# boardV2.net
KiCad netlist of a schematic drawn in EAGLE
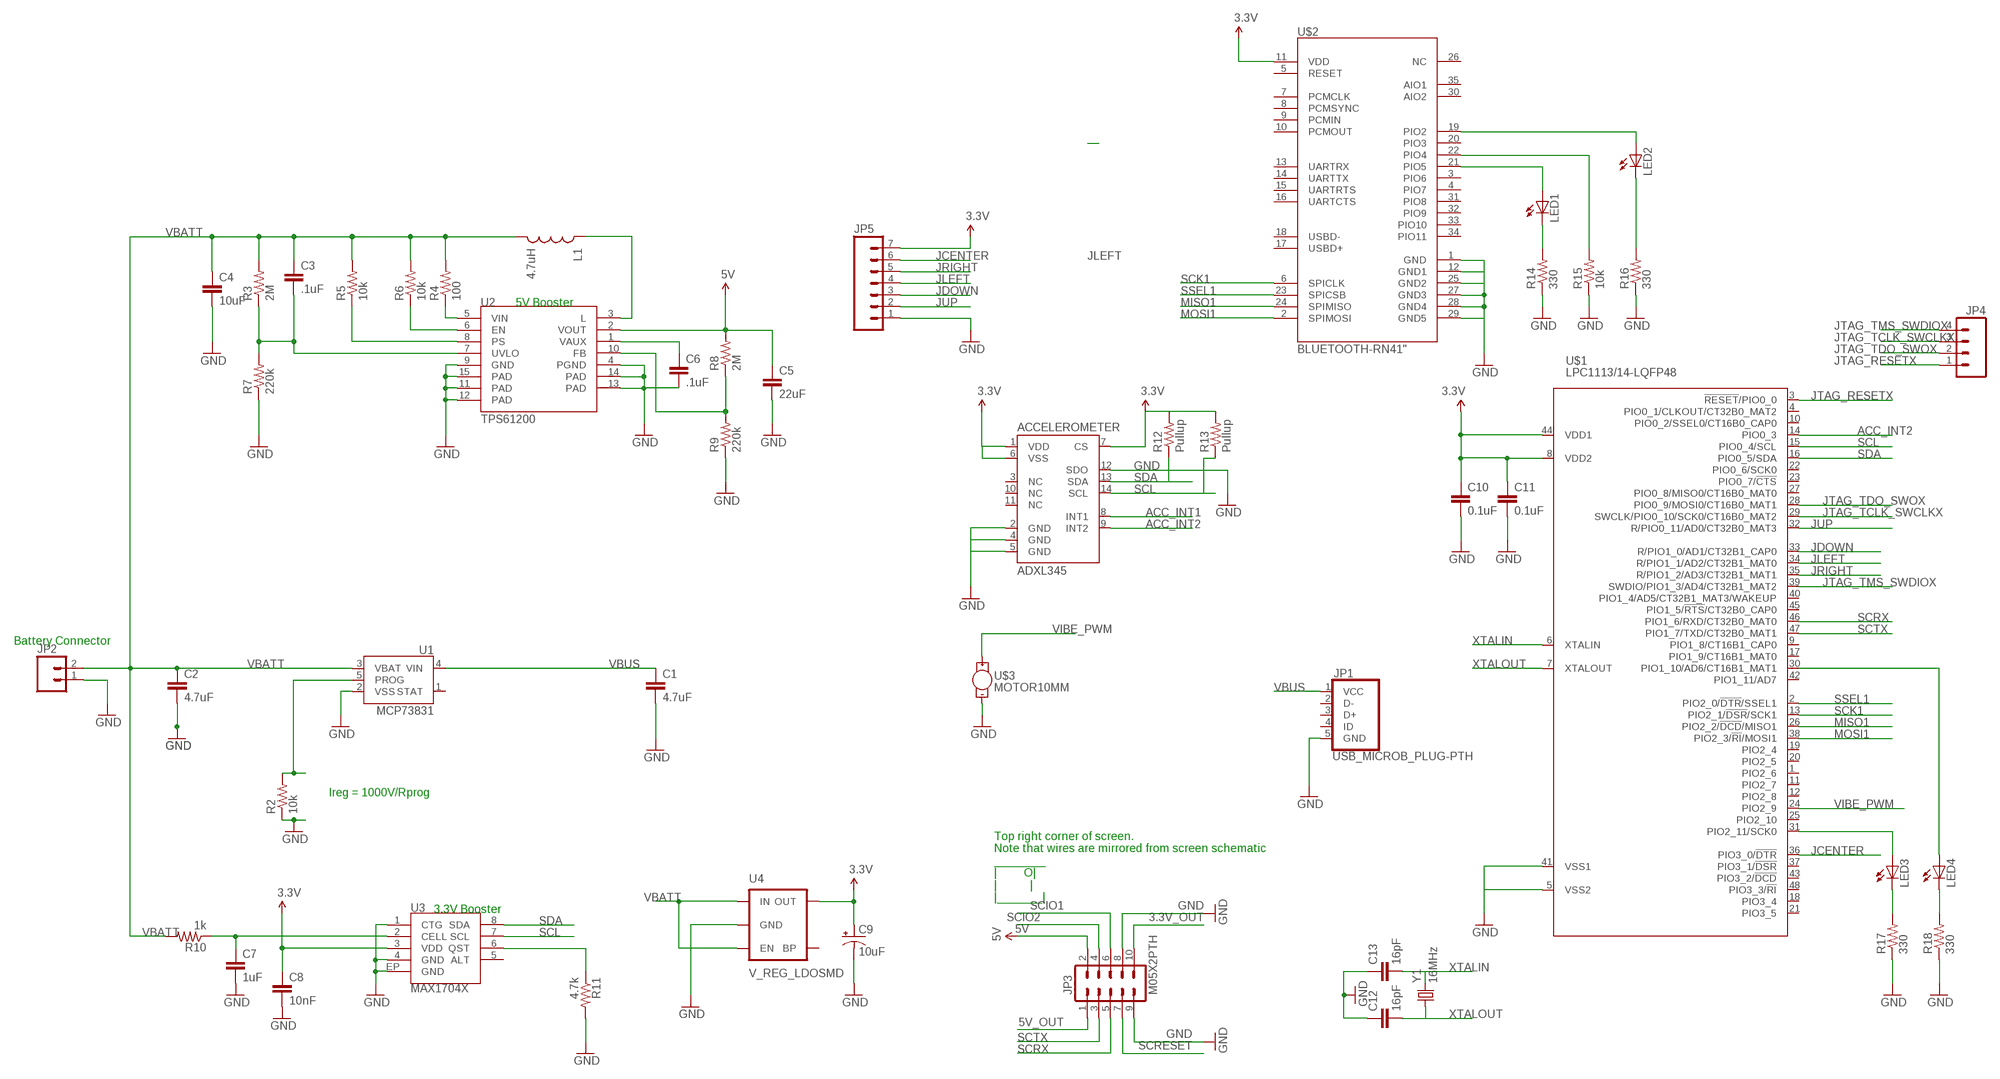
[diagram p0: schematic, sheet 1]

(export (version "E")
  (design (tool "Eeschema 10.0.6"))
  (components
    (comp (ref "ACCELEROMETER")
      (value "ADXL345")
      (footprint "eagle-import:LGA14")
      (libsource (lib "eagle-import") (part "ADXL345"))
    )
    (comp (ref "C1")
      (value "4.7uF")
      (footprint "eagle-import:0402-CAP")
      (libsource (lib "eagle-import") (part "CAP0402-CAP"))
    )
    (comp (ref "C2")
      (value "4.7uF")
      (footprint "eagle-import:0402-CAP")
      (libsource (lib "eagle-import") (part "CAP0402-CAP"))
    )
    (comp (ref "C3")
      (value ".1uF")
      (footprint "eagle-import:0402-CAP")
      (libsource (lib "eagle-import") (part "CAP0402-CAP"))
    )
    (comp (ref "C4")
      (value "10uF")
      (footprint "eagle-import:0402-CAP")
      (libsource (lib "eagle-import") (part "CAP0402-CAP"))
    )
    (comp (ref "C5")
      (value "22uF")
      (footprint "eagle-import:0402-CAP")
      (libsource (lib "eagle-import") (part "CAP0402-CAP"))
    )
    (comp (ref "C6")
      (value ".1uF")
      (footprint "eagle-import:0402-CAP")
      (libsource (lib "eagle-import") (part "CAP0402-CAP"))
    )
    (comp (ref "C7")
      (value "1uF")
      (footprint "eagle-import:0402-CAP")
      (libsource (lib "eagle-import") (part "CAP0402-CAP"))
    )
    (comp (ref "C8")
      (value "10nF")
      (footprint "eagle-import:0402-CAP")
      (libsource (lib "eagle-import") (part "CAP0402-CAP"))
    )
    (comp (ref "C9")
      (value "10uF")
      (footprint "eagle-import:EIA3216")
      (libsource (lib "eagle-import") (part "10UF-TANT"))
    )
    (comp (ref "C10")
      (value "0.1uF")
      (footprint "eagle-import:0402-CAP")
      (libsource (lib "eagle-import") (part ".1UF-CER"))
    )
    (comp (ref "C11")
      (value "0.1uF")
      (footprint "eagle-import:0402-CAP")
      (libsource (lib "eagle-import") (part ".1UF-CER"))
    )
    (comp (ref "C12")
      (value "16pF")
      (footprint "eagle-import:0402-CAP")
      (libsource (lib "eagle-import") (part "CAP0402-CAP"))
    )
    (comp (ref "C13")
      (value "16pF")
      (footprint "eagle-import:0402-CAP")
      (libsource (lib "eagle-import") (part "CAP0402-CAP"))
    )
    (comp (ref "JP1")
      (value "USB_MICROB_PLUG-PTH")
      (footprint "eagle-import:MICRO-B-RA-TH")
      (libsource (lib "eagle-import") (part "USB_MICROB_PLUG-PTH"))
    )
    (comp (ref "JP2")
      (value "M02-JST-2-PTH-NO_SILK")
      (footprint "eagle-import:JST-2-PTH-NS")
      (libsource (lib "eagle-import") (part "M02-JST-2-PTH-NO_SILK"))
    )
    (comp (ref "JP3")
      (value "M05X2PTH")
      (footprint "eagle-import:AVR_ICSP")
      (libsource (lib "eagle-import") (part "M05X2PTH"))
    )
    (comp (ref "JP4")
      (value "M04POLAR")
      (footprint "eagle-import:MOLEX-1X4")
      (libsource (lib "eagle-import") (part "M04POLAR"))
    )
    (comp (ref "JP5")
      (value "M07")
      (footprint "eagle-import:1X07")
      (libsource (lib "eagle-import") (part "M07"))
    )
    (comp (ref "L1")
      (value "4.7uH")
      (footprint "eagle-import:C0402")
      (libsource (lib "eagle-import") (part "INDUCTOR0402"))
    )
    (comp (ref "LED1")
      (value "LED0603")
      (footprint "eagle-import:LED-0603")
      (libsource (lib "eagle-import") (part "LED0603"))
    )
    (comp (ref "LED2")
      (value "LED0603")
      (footprint "eagle-import:LED-0603")
      (libsource (lib "eagle-import") (part "LED0603"))
    )
    (comp (ref "LED3")
      (value "LED0603")
      (footprint "eagle-import:LED-0603")
      (libsource (lib "eagle-import") (part "LED0603"))
    )
    (comp (ref "LED4")
      (value "LED0603")
      (footprint "eagle-import:LED-0603")
      (libsource (lib "eagle-import") (part "LED0603"))
    )
    (comp (ref "R2")
      (value "10k")
      (footprint "eagle-import:0402-RES")
      (libsource (lib "eagle-import") (part "RESISTOR0402-RES"))
    )
    (comp (ref "R3")
      (value "2M")
      (footprint "eagle-import:0402-RES")
      (libsource (lib "eagle-import") (part "RESISTOR0402-RES"))
    )
    (comp (ref "R4")
      (value "100")
      (footprint "eagle-import:0402-RES")
      (libsource (lib "eagle-import") (part "RESISTOR0402-RES"))
    )
    (comp (ref "R5")
      (value "10k")
      (footprint "eagle-import:0402-RES")
      (libsource (lib "eagle-import") (part "RESISTOR0402-RES"))
    )
    (comp (ref "R6")
      (value "10k")
      (footprint "eagle-import:0402-RES")
      (libsource (lib "eagle-import") (part "RESISTOR0402-RES"))
    )
    (comp (ref "R7")
      (value "220k")
      (footprint "eagle-import:0402-RES")
      (libsource (lib "eagle-import") (part "RESISTOR0402-RES"))
    )
    (comp (ref "R8")
      (value "2M")
      (footprint "eagle-import:0402-RES")
      (libsource (lib "eagle-import") (part "RESISTOR0402-RES"))
    )
    (comp (ref "R9")
      (value "220k")
      (footprint "eagle-import:0402-RES")
      (libsource (lib "eagle-import") (part "RESISTOR0402-RES"))
    )
    (comp (ref "R10")
      (value "1k")
      (footprint "eagle-import:0402-RES")
      (libsource (lib "eagle-import") (part "RESISTOR0402-RES"))
    )
    (comp (ref "R11")
      (value "4.7k")
      (footprint "eagle-import:0402-RES")
      (libsource (lib "eagle-import") (part "RESISTOR0402-RES"))
    )
    (comp (ref "R12")
      (value "Pullup")
      (footprint "eagle-import:0402-RES")
      (libsource (lib "eagle-import") (part "RESISTOR0402-RES"))
    )
    (comp (ref "R13")
      (value "Pullup")
      (footprint "eagle-import:0402-RES")
      (libsource (lib "eagle-import") (part "RESISTOR0402-RES"))
    )
    (comp (ref "R14")
      (value "330")
      (footprint "eagle-import:0402-RES")
      (libsource (lib "eagle-import") (part "RESISTOR0402-RES"))
    )
    (comp (ref "R15")
      (value "10k")
      (footprint "eagle-import:0402-RES")
      (libsource (lib "eagle-import") (part "RESISTOR0402-RES"))
    )
    (comp (ref "R16")
      (value "330")
      (footprint "eagle-import:0402-RES")
      (libsource (lib "eagle-import") (part "RESISTOR0402-RES"))
    )
    (comp (ref "R17")
      (value "330")
      (footprint "eagle-import:0402-RES")
      (libsource (lib "eagle-import") (part "RESISTOR0402-RES"))
    )
    (comp (ref "R18")
      (value "330")
      (footprint "eagle-import:0402-RES")
      (libsource (lib "eagle-import") (part "RESISTOR0402-RES"))
    )
    (comp (ref "U$1")
      (value "LPC1113/14-LQFP48")
      (footprint "eagle-import:LQFP48")
      (libsource (lib "eagle-import") (part "LPC1113/14-LQFP48"))
    )
    (comp (ref "U$2")
      (value "BLUETOOTH-RN41\"")
      (footprint "eagle-import:RN41")
      (libsource (lib "eagle-import") (part "BLUETOOTH-RN41{dblquote}"))
    )
    (comp (ref "U$3")
      (value "MOTOR10MM")
      (footprint "eagle-import:VIBE-MOTOR-10MM")
      (libsource (lib "eagle-import") (part "MOTOR10MM"))
    )
    (comp (ref "U1")
      (value "MCP73831")
      (footprint "eagle-import:SOT23-5")
      (libsource (lib "eagle-import") (part "MCP73831"))
    )
    (comp (ref "U2")
      (value "TPS61200")
      (footprint "eagle-import:QFN-10_PAD")
      (libsource (lib "eagle-import") (part "TPS61200"))
    )
    (comp (ref "U3")
      (value "MAX1704X")
      (footprint "eagle-import:TDFN-8")
      (libsource (lib "eagle-import") (part "MAX1704X"))
    )
    (comp (ref "U4")
      (value "V_REG_LDOSMD")
      (footprint "eagle-import:SOT23-5")
      (libsource (lib "eagle-import") (part "V_REG_LDOSMD"))
    )
    (comp (ref "Y1")
      (value "16MHz")
      (footprint "eagle-import:CRYSTAL-SMD-5X3")
      (libsource (lib "eagle-import") (part "CRYSTAL5X3"))
    )
  )
  (nets
    (net (code "1") (name "/3.3V_OUT") (class "Default")
      (node (ref "JP3") (pin "10") (pinfunction "10_10") (pintype "passive"))
    )
    (net (code "2") (name "/5V_OUT") (class "Default")
      (node (ref "JP3") (pin "1") (pinfunction "1_1") (pintype "passive"))
    )
    (net (code "3") (name "/ACC_INT1") (class "Default")
      (node (ref "ACCELEROMETER") (pin "8") (pinfunction "INT1_8") (pintype "bidirectional"))
    )
    (net (code "4") (name "/ACC_INT2") (class "Default")
      (node (ref "ACCELEROMETER") (pin "9") (pinfunction "INT2_9") (pintype "bidirectional"))
      (node (ref "U$1") (pin "14") (pinfunction "PIO0_3_14") (pintype "bidirectional"))
    )
    (net (code "5") (name "/JCENTER") (class "Default")
      (node (ref "JP5") (pin "6") (pinfunction "6_6") (pintype "passive"))
      (node (ref "U$1") (pin "36") (pinfunction "PIO3_0/~{DTR}_36") (pintype "bidirectional"))
    )
    (net (code "6") (name "/JDOWN") (class "Default")
      (node (ref "JP5") (pin "3") (pinfunction "3_3") (pintype "passive"))
      (node (ref "U$1") (pin "33") (pinfunction "R/PIO1_0/AD1/CT32B1_CAP0_33") (pintype "bidirectional"))
    )
    (net (code "7") (name "/JLEFT") (class "Default")
      (node (ref "JP5") (pin "4") (pinfunction "4_4") (pintype "passive"))
      (node (ref "U$1") (pin "34") (pinfunction "R/PIO1_1/AD2/CT32B1_MAT0_34") (pintype "bidirectional"))
    )
    (net (code "8") (name "/JRIGHT") (class "Default")
      (node (ref "JP5") (pin "5") (pinfunction "5_5") (pintype "passive"))
      (node (ref "U$1") (pin "35") (pinfunction "R/PIO1_2/AD3/CT32B1_MAT1_35") (pintype "bidirectional"))
    )
    (net (code "9") (name "/JTAG_RESETX") (class "Default")
      (node (ref "JP4") (pin "1") (pinfunction "1_1") (pintype "passive"))
      (node (ref "U$1") (pin "3") (pinfunction "~{RESET}/PIO0_0_3") (pintype "bidirectional"))
    )
    (net (code "10") (name "/JTAG_TCLK_SWCLKX") (class "Default")
      (node (ref "JP4") (pin "3") (pinfunction "3_3") (pintype "passive"))
      (node (ref "U$1") (pin "29") (pinfunction "SWCLK/PIO0_10/SCK0/CT16B0_MAT2_29") (pintype "bidirectional"))
    )
    (net (code "11") (name "/JTAG_TDO_SWOX") (class "Default")
      (node (ref "JP4") (pin "2") (pinfunction "2_2") (pintype "passive"))
      (node (ref "U$1") (pin "28") (pinfunction "PIO0_9/MOSI0/CT16B0_MAT1_28") (pintype "bidirectional"))
    )
    (net (code "12") (name "/JTAG_TMS_SWDIOX") (class "Default")
      (node (ref "JP4") (pin "4") (pinfunction "4_4") (pintype "passive"))
      (node (ref "U$1") (pin "39") (pinfunction "SWDIO/PIO1_3/AD4/CT32B1_MAT2_39") (pintype "bidirectional"))
    )
    (net (code "13") (name "/JUP") (class "Default")
      (node (ref "JP5") (pin "2") (pinfunction "2_2") (pintype "passive"))
      (node (ref "U$1") (pin "32") (pinfunction "R/PIO0_11/AD0/CT32B0_MAT3_32") (pintype "bidirectional"))
    )
    (net (code "14") (name "/MISO1") (class "Default")
      (node (ref "U$1") (pin "26") (pinfunction "PIO2_2/~{DCD}/MISO1_26") (pintype "bidirectional"))
      (node (ref "U$2") (pin "24") (pinfunction "SPIMISO_24") (pintype "bidirectional"))
    )
    (net (code "15") (name "/MOSI1") (class "Default")
      (node (ref "U$1") (pin "38") (pinfunction "PIO2_3/~{RI}/MOSI1_38") (pintype "bidirectional"))
      (node (ref "U$2") (pin "2") (pinfunction "SPIMOSI_2") (pintype "bidirectional"))
    )
    (net (code "16") (name "/SCIO1") (class "Default")
      (node (ref "JP3") (pin "6") (pinfunction "6_6") (pintype "passive"))
    )
    (net (code "17") (name "/SCIO2") (class "Default")
      (node (ref "JP3") (pin "4") (pinfunction "4_4") (pintype "passive"))
    )
    (net (code "18") (name "/SCK1") (class "Default")
      (node (ref "U$1") (pin "13") (pinfunction "PIO2_1/~{DSR}/SCK1_13") (pintype "bidirectional"))
      (node (ref "U$2") (pin "6") (pinfunction "SPICLK_6") (pintype "bidirectional"))
    )
    (net (code "19") (name "/SCL") (class "Default")
      (node (ref "ACCELEROMETER") (pin "14") (pinfunction "SCL_14") (pintype "bidirectional"))
      (node (ref "R13") (pin "1") (pinfunction "1_1") (pintype "passive"))
      (node (ref "U$1") (pin "15") (pinfunction "PIO0_4/SCL_15") (pintype "bidirectional"))
      (node (ref "U3") (pin "7") (pinfunction "SCL_7") (pintype "bidirectional"))
    )
    (net (code "20") (name "/SCRESET") (class "Default")
      (node (ref "JP3") (pin "7") (pinfunction "7_7") (pintype "passive"))
    )
    (net (code "21") (name "/SCRX") (class "Default")
      (node (ref "JP3") (pin "5") (pinfunction "5_5") (pintype "passive"))
      (node (ref "U$1") (pin "46") (pinfunction "PIO1_6/RXD/CT32B0_MAT0_46") (pintype "bidirectional"))
    )
    (net (code "22") (name "/SCTX") (class "Default")
      (node (ref "JP3") (pin "3") (pinfunction "3_3") (pintype "passive"))
      (node (ref "U$1") (pin "47") (pinfunction "PIO1_7/TXD/CT32B0_MAT1_47") (pintype "bidirectional"))
    )
    (net (code "23") (name "/SDA") (class "Default")
      (node (ref "ACCELEROMETER") (pin "13") (pinfunction "SDA_13") (pintype "bidirectional"))
      (node (ref "R12") (pin "1") (pinfunction "1_1") (pintype "passive"))
      (node (ref "U$1") (pin "16") (pinfunction "PIO0_5/SDA_16") (pintype "bidirectional"))
      (node (ref "U3") (pin "8") (pinfunction "SDA_8") (pintype "bidirectional"))
    )
    (net (code "24") (name "/SSEL1") (class "Default")
      (node (ref "U$1") (pin "2") (pinfunction "PIO2_0/~{DTR}/SSEL1_2") (pintype "bidirectional"))
      (node (ref "U$2") (pin "23") (pinfunction "SPICSB_23") (pintype "bidirectional"))
    )
    (net (code "25") (name "/VBATT") (class "Default")
      (node (ref "C2") (pin "1") (pinfunction "1_1") (pintype "passive"))
      (node (ref "C3") (pin "1") (pinfunction "1_1") (pintype "passive"))
      (node (ref "C4") (pin "1") (pinfunction "1_1") (pintype "passive"))
      (node (ref "JP2") (pin "2") (pinfunction "2_2") (pintype "passive"))
      (node (ref "L1") (pin "2") (pinfunction "2_2") (pintype "passive"))
      (node (ref "R10") (pin "2") (pinfunction "2_2") (pintype "passive"))
      (node (ref "R3") (pin "2") (pinfunction "2_2") (pintype "passive"))
      (node (ref "R4") (pin "2") (pinfunction "2_2") (pintype "passive"))
      (node (ref "R5") (pin "2") (pinfunction "2_2") (pintype "passive"))
      (node (ref "R6") (pin "2") (pinfunction "2_2") (pintype "passive"))
      (node (ref "U1") (pin "3") (pinfunction "VBAT_3") (pintype "power_in"))
      (node (ref "U4") (pin "1") (pinfunction "IN_1") (pintype "input"))
      (node (ref "U4") (pin "3") (pinfunction "EN_3") (pintype "input"))
    )
    (net (code "26") (name "/VBUS") (class "Default")
      (node (ref "C1") (pin "1") (pinfunction "1_1") (pintype "passive"))
      (node (ref "JP1") (pin "1") (pinfunction "VCC_1") (pintype "bidirectional"))
      (node (ref "U1") (pin "4") (pinfunction "VIN_4") (pintype "power_in"))
    )
    (net (code "27") (name "/VIBE_PWM") (class "Default")
      (node (ref "U$1") (pin "24") (pinfunction "PIO2_9_24") (pintype "bidirectional"))
      (node (ref "U$3") (pin "+") (pinfunction "+_+") (pintype "bidirectional"))
    )
    (net (code "28") (name "/XTALIN") (class "Default")
      (node (ref "C13") (pin "2") (pinfunction "2_2") (pintype "passive"))
      (node (ref "U$1") (pin "6") (pinfunction "XTALIN_6") (pintype "passive"))
      (node (ref "Y1") (pin "3") (pinfunction "2_3") (pintype "passive"))
    )
    (net (code "29") (name "/XTALOUT") (class "Default")
      (node (ref "C12") (pin "2") (pinfunction "2_2") (pintype "passive"))
      (node (ref "U$1") (pin "7") (pinfunction "XTALOUT_7") (pintype "passive"))
      (node (ref "Y1") (pin "1") (pinfunction "1_1") (pintype "passive"))
    )
    (net (code "30") (name "3.3V") (class "Default")
      (node (ref "ACCELEROMETER") (pin "1") (pinfunction "VDD_1") (pintype "bidirectional"))
      (node (ref "ACCELEROMETER") (pin "6") (pinfunction "VSS_6") (pintype "bidirectional"))
      (node (ref "ACCELEROMETER") (pin "7") (pinfunction "CS_7") (pintype "bidirectional"))
      (node (ref "C10") (pin "1") (pinfunction "1_1") (pintype "passive"))
      (node (ref "C11") (pin "1") (pinfunction "1_1") (pintype "passive"))
      (node (ref "C8") (pin "1") (pinfunction "1_1") (pintype "passive"))
      (node (ref "C9") (pin "A") (pinfunction "+_A") (pintype "passive"))
      (node (ref "JP5") (pin "7") (pinfunction "7_7") (pintype "passive"))
      (node (ref "R12") (pin "2") (pinfunction "2_2") (pintype "passive"))
      (node (ref "R13") (pin "2") (pinfunction "2_2") (pintype "passive"))
      (node (ref "U$1") (pin "44") (pinfunction "VDD1_44") (pintype "power_in"))
      (node (ref "U$1") (pin "8") (pinfunction "VDD2_8") (pintype "power_in"))
      (node (ref "U$2") (pin "11") (pinfunction "VDD_11") (pintype "bidirectional"))
      (node (ref "U3") (pin "3") (pinfunction "VDD_3") (pintype "bidirectional"))
      (node (ref "U4") (pin "5") (pinfunction "OUT_5") (pintype "passive"))
    )
    (net (code "31") (name "5V") (class "Default")
      (node (ref "C5") (pin "1") (pinfunction "1_1") (pintype "passive"))
      (node (ref "JP3") (pin "2") (pinfunction "2_2") (pintype "passive"))
      (node (ref "R8") (pin "2") (pinfunction "2_2") (pintype "passive"))
      (node (ref "U2") (pin "2") (pinfunction "VOUT_2") (pintype "passive"))
    )
    (net (code "32") (name "GND") (class "Default")
      (node (ref "ACCELEROMETER") (pin "12") (pinfunction "SDO_12") (pintype "bidirectional"))
      (node (ref "ACCELEROMETER") (pin "2") (pinfunction "GND_2") (pintype "bidirectional"))
      (node (ref "ACCELEROMETER") (pin "4") (pinfunction "GND_4") (pintype "bidirectional"))
      (node (ref "ACCELEROMETER") (pin "5") (pinfunction "GND_5") (pintype "bidirectional"))
      (node (ref "C1") (pin "2") (pinfunction "2_2") (pintype "passive"))
      (node (ref "C10") (pin "2") (pinfunction "2_2") (pintype "passive"))
      (node (ref "C11") (pin "2") (pinfunction "2_2") (pintype "passive"))
      (node (ref "C12") (pin "1") (pinfunction "1_1") (pintype "passive"))
      (node (ref "C13") (pin "1") (pinfunction "1_1") (pintype "passive"))
      (node (ref "C2") (pin "2") (pinfunction "2_2") (pintype "passive"))
      (node (ref "C4") (pin "2") (pinfunction "2_2") (pintype "passive"))
      (node (ref "C5") (pin "2") (pinfunction "2_2") (pintype "passive"))
      (node (ref "C6") (pin "2") (pinfunction "2_2") (pintype "passive"))
      (node (ref "C7") (pin "2") (pinfunction "2_2") (pintype "passive"))
      (node (ref "C8") (pin "2") (pinfunction "2_2") (pintype "passive"))
      (node (ref "C9") (pin "C") (pinfunction "-_C") (pintype "passive"))
      (node (ref "JP1") (pin "5") (pinfunction "GND_5") (pintype "bidirectional"))
      (node (ref "JP2") (pin "1") (pinfunction "1_1") (pintype "passive"))
      (node (ref "JP3") (pin "8") (pinfunction "8_8") (pintype "passive"))
      (node (ref "JP3") (pin "9") (pinfunction "9_9") (pintype "passive"))
      (node (ref "JP5") (pin "1") (pinfunction "1_1") (pintype "passive"))
      (node (ref "R11") (pin "2") (pinfunction "2_2") (pintype "passive"))
      (node (ref "R14") (pin "1") (pinfunction "1_1") (pintype "passive"))
      (node (ref "R15") (pin "1") (pinfunction "1_1") (pintype "passive"))
      (node (ref "R16") (pin "1") (pinfunction "1_1") (pintype "passive"))
      (node (ref "R17") (pin "1") (pinfunction "1_1") (pintype "passive"))
      (node (ref "R18") (pin "1") (pinfunction "1_1") (pintype "passive"))
      (node (ref "R2") (pin "1") (pinfunction "1_1") (pintype "passive"))
      (node (ref "R7") (pin "1") (pinfunction "1_1") (pintype "passive"))
      (node (ref "R9") (pin "1") (pinfunction "1_1") (pintype "passive"))
      (node (ref "U$1") (pin "41") (pinfunction "VSS1_41") (pintype "power_in"))
      (node (ref "U$1") (pin "5") (pinfunction "VSS2_5") (pintype "power_in"))
      (node (ref "U$2") (pin "1") (pinfunction "GND_1") (pintype "bidirectional"))
      (node (ref "U$2") (pin "12") (pinfunction "GND1_12") (pintype "bidirectional"))
      (node (ref "U$2") (pin "25") (pinfunction "GND2_25") (pintype "bidirectional"))
      (node (ref "U$2") (pin "27") (pinfunction "GND3_27") (pintype "bidirectional"))
      (node (ref "U$2") (pin "28") (pinfunction "GND4_28") (pintype "bidirectional"))
      (node (ref "U$2") (pin "29") (pinfunction "GND5_29") (pintype "bidirectional"))
      (node (ref "U$3") (pin "-") (pinfunction "-_-") (pintype "bidirectional"))
      (node (ref "U1") (pin "2") (pinfunction "VSS_2") (pintype "power_in"))
      (node (ref "U2") (pin "11") (pinfunction "PAD_11") (pintype "power_in"))
      (node (ref "U2") (pin "12") (pinfunction "PAD_12") (pintype "power_in"))
      (node (ref "U2") (pin "13") (pinfunction "PAD_13") (pintype "power_in"))
      (node (ref "U2") (pin "14") (pinfunction "PAD_14") (pintype "power_in"))
      (node (ref "U2") (pin "15") (pinfunction "PAD_15") (pintype "power_in"))
      (node (ref "U2") (pin "4") (pinfunction "PGND_4") (pintype "power_in"))
      (node (ref "U2") (pin "9") (pinfunction "GND_9") (pintype "power_in"))
      (node (ref "U3") (pin "1") (pinfunction "CTG_1") (pintype "bidirectional"))
      (node (ref "U3") (pin "4") (pinfunction "GND_4") (pintype "bidirectional"))
      (node (ref "U3") (pin "EP") (pinfunction "GND_EP") (pintype "bidirectional"))
      (node (ref "U4") (pin "2") (pinfunction "GND_2") (pintype "input"))
    )
    (net (code "33") (name "Net-(LED1-PadC)") (class "Default")
      (node (ref "LED1") (pin "C") (pinfunction "C_C") (pintype "passive"))
      (node (ref "R14") (pin "2") (pinfunction "2_2") (pintype "passive"))
    )
    (net (code "34") (name "Net-(LED2-PadC)") (class "Default")
      (node (ref "LED2") (pin "C") (pinfunction "C_C") (pintype "passive"))
      (node (ref "R16") (pin "2") (pinfunction "2_2") (pintype "passive"))
    )
    (net (code "35") (name "Net-(LED3-PadC)") (class "Default")
      (node (ref "LED3") (pin "C") (pinfunction "C_C") (pintype "passive"))
      (node (ref "R17") (pin "2") (pinfunction "2_2") (pintype "passive"))
    )
    (net (code "36") (name "Net-(LED4-PadC)") (class "Default")
      (node (ref "LED4") (pin "C") (pinfunction "C_C") (pintype "passive"))
      (node (ref "R18") (pin "2") (pinfunction "2_2") (pintype "passive"))
    )
    (net (code "37") (name "Net-(U$1-PIO1_10{slash}AD6{slash}CT16B1_MAT1)") (class "Default")
      (node (ref "LED4") (pin "A") (pinfunction "A_A") (pintype "passive"))
      (node (ref "U$1") (pin "30") (pinfunction "PIO1_10/AD6/CT16B1_MAT1_30") (pintype "bidirectional"))
    )
    (net (code "38") (name "Net-(U$1-PIO2_11{slash}SCK0)") (class "Default")
      (node (ref "LED3") (pin "A") (pinfunction "A_A") (pintype "passive"))
      (node (ref "U$1") (pin "31") (pinfunction "PIO2_11/SCK0_31") (pintype "bidirectional"))
    )
    (net (code "39") (name "Net-(U$2-PIO2)") (class "Default")
      (node (ref "LED2") (pin "A") (pinfunction "A_A") (pintype "passive"))
      (node (ref "U$2") (pin "19") (pinfunction "PIO2_19") (pintype "bidirectional"))
    )
    (net (code "40") (name "Net-(U$2-PIO4)") (class "Default")
      (node (ref "R15") (pin "2") (pinfunction "2_2") (pintype "passive"))
      (node (ref "U$2") (pin "22") (pinfunction "PIO4_22") (pintype "bidirectional"))
    )
    (net (code "41") (name "Net-(U$2-PIO5)") (class "Default")
      (node (ref "LED1") (pin "A") (pinfunction "A_A") (pintype "passive"))
      (node (ref "U$2") (pin "21") (pinfunction "PIO5_21") (pintype "bidirectional"))
    )
    (net (code "42") (name "Net-(U1-PROG)") (class "Default")
      (node (ref "R2") (pin "2") (pinfunction "2_2") (pintype "passive"))
      (node (ref "U1") (pin "5") (pinfunction "PROG_5") (pintype "input"))
    )
    (net (code "43") (name "Net-(U2-EN)") (class "Default")
      (node (ref "R6") (pin "1") (pinfunction "1_1") (pintype "passive"))
      (node (ref "U2") (pin "6") (pinfunction "EN_6") (pintype "input"))
    )
    (net (code "44") (name "Net-(U2-FB)") (class "Default")
      (node (ref "R8") (pin "1") (pinfunction "1_1") (pintype "passive"))
      (node (ref "R9") (pin "2") (pinfunction "2_2") (pintype "passive"))
      (node (ref "U2") (pin "10") (pinfunction "FB_10") (pintype "passive"))
    )
    (net (code "45") (name "Net-(U2-L)") (class "Default")
      (node (ref "L1") (pin "1") (pinfunction "1_1") (pintype "passive"))
      (node (ref "U2") (pin "3") (pinfunction "L_3") (pintype "passive"))
    )
    (net (code "46") (name "Net-(U2-PS)") (class "Default")
      (node (ref "R5") (pin "1") (pinfunction "1_1") (pintype "passive"))
      (node (ref "U2") (pin "8") (pinfunction "PS_8") (pintype "input"))
    )
    (net (code "47") (name "Net-(U2-UVLO)") (class "Default")
      (node (ref "C3") (pin "2") (pinfunction "2_2") (pintype "passive"))
      (node (ref "R3") (pin "1") (pinfunction "1_1") (pintype "passive"))
      (node (ref "R7") (pin "2") (pinfunction "2_2") (pintype "passive"))
      (node (ref "U2") (pin "7") (pinfunction "UVLO_7") (pintype "passive"))
    )
    (net (code "48") (name "Net-(U2-VAUX)") (class "Default")
      (node (ref "C6") (pin "1") (pinfunction "1_1") (pintype "passive"))
      (node (ref "U2") (pin "1") (pinfunction "VAUX_1") (pintype "passive"))
    )
    (net (code "49") (name "Net-(U2-VIN)") (class "Default")
      (node (ref "R4") (pin "1") (pinfunction "1_1") (pintype "passive"))
      (node (ref "U2") (pin "5") (pinfunction "VIN_5") (pintype "power_in"))
    )
    (net (code "50") (name "Net-(U3-CELL)") (class "Default")
      (node (ref "C7") (pin "1") (pinfunction "1_1") (pintype "passive"))
      (node (ref "R10") (pin "1") (pinfunction "1_1") (pintype "passive"))
      (node (ref "U3") (pin "2") (pinfunction "CELL_2") (pintype "bidirectional"))
    )
    (net (code "51") (name "Net-(U3-QST)") (class "Default")
      (node (ref "R11") (pin "1") (pinfunction "1_1") (pintype "passive"))
      (node (ref "U3") (pin "6") (pinfunction "QST_6") (pintype "bidirectional"))
    )
    (net (code "52") (name "unconnected-(ACCELEROMETER-NC-Pad3)") (class "Default")
      (node (ref "ACCELEROMETER") (pin "3") (pinfunction "NC_3") (pintype "bidirectional"))
    )
    (net (code "53") (name "unconnected-(ACCELEROMETER-NC-Pad10)") (class "Default")
      (node (ref "ACCELEROMETER") (pin "10") (pinfunction "NC_10") (pintype "bidirectional"))
    )
    (net (code "54") (name "unconnected-(ACCELEROMETER-NC-Pad11)") (class "Default")
      (node (ref "ACCELEROMETER") (pin "11") (pinfunction "NC_11") (pintype "bidirectional"))
    )
    (net (code "55") (name "unconnected-(JP1-D+-Pad3)") (class "Default")
      (node (ref "JP1") (pin "3") (pinfunction "D+_3") (pintype "bidirectional"))
    )
    (net (code "56") (name "unconnected-(JP1-D--Pad2)") (class "Default")
      (node (ref "JP1") (pin "2") (pinfunction "D-_2") (pintype "bidirectional"))
    )
    (net (code "57") (name "unconnected-(JP1-ID-Pad4)") (class "Default")
      (node (ref "JP1") (pin "4") (pinfunction "ID_4") (pintype "bidirectional"))
    )
    (net (code "58") (name "unconnected-(U$1-PIO0_1{slash}CLKOUT{slash}CT32B0_MAT2-Pad4)") (class "Default")
      (node (ref "U$1") (pin "4") (pinfunction "PIO0_1/CLKOUT/CT32B0_MAT2_4") (pintype "bidirectional"))
    )
    (net (code "59") (name "unconnected-(U$1-PIO0_2{slash}SSEL0{slash}CT16B0_CAP0-Pad10)") (class "Default")
      (node (ref "U$1") (pin "10") (pinfunction "PIO0_2/SSEL0/CT16B0_CAP0_10") (pintype "bidirectional"))
    )
    (net (code "60") (name "unconnected-(U$1-PIO0_6{slash}SCK0-Pad22)") (class "Default")
      (node (ref "U$1") (pin "22") (pinfunction "PIO0_6/SCK0_22") (pintype "bidirectional"))
    )
    (net (code "61") (name "unconnected-(U$1-PIO0_7{slash}~{CTS}-Pad23)") (class "Default")
      (node (ref "U$1") (pin "23") (pinfunction "PIO0_7/~{CTS}_23") (pintype "bidirectional"))
    )
    (net (code "62") (name "unconnected-(U$1-PIO0_8{slash}MISO0{slash}CT16B0_MAT0-Pad27)") (class "Default")
      (node (ref "U$1") (pin "27") (pinfunction "PIO0_8/MISO0/CT16B0_MAT0_27") (pintype "bidirectional"))
    )
    (net (code "63") (name "unconnected-(U$1-PIO1_4{slash}AD5{slash}CT32B1_MAT3{slash}WAKEUP-Pad40)") (class "Default")
      (node (ref "U$1") (pin "40") (pinfunction "PIO1_4/AD5/CT32B1_MAT3/WAKEUP_40") (pintype "bidirectional"))
    )
    (net (code "64") (name "unconnected-(U$1-PIO1_5{slash}~{RTS}{slash}CT32B0_CAP0-Pad45)") (class "Default")
      (node (ref "U$1") (pin "45") (pinfunction "PIO1_5/~{RTS}/CT32B0_CAP0_45") (pintype "bidirectional"))
    )
    (net (code "65") (name "unconnected-(U$1-PIO1_8{slash}CT16B1_CAP0-Pad9)") (class "Default")
      (node (ref "U$1") (pin "9") (pinfunction "PIO1_8/CT16B1_CAP0_9") (pintype "bidirectional"))
    )
    (net (code "66") (name "unconnected-(U$1-PIO1_9{slash}CT16B1_MAT0-Pad17)") (class "Default")
      (node (ref "U$1") (pin "17") (pinfunction "PIO1_9/CT16B1_MAT0_17") (pintype "bidirectional"))
    )
    (net (code "67") (name "unconnected-(U$1-PIO1_11{slash}AD7-Pad42)") (class "Default")
      (node (ref "U$1") (pin "42") (pinfunction "PIO1_11/AD7_42") (pintype "bidirectional"))
    )
    (net (code "68") (name "unconnected-(U$1-PIO2_4-Pad19)") (class "Default")
      (node (ref "U$1") (pin "19") (pinfunction "PIO2_4_19") (pintype "bidirectional"))
    )
    (net (code "69") (name "unconnected-(U$1-PIO2_5-Pad20)") (class "Default")
      (node (ref "U$1") (pin "20") (pinfunction "PIO2_5_20") (pintype "bidirectional"))
    )
    (net (code "70") (name "unconnected-(U$1-PIO2_6-Pad1)") (class "Default")
      (node (ref "U$1") (pin "1") (pinfunction "PIO2_6_1") (pintype "bidirectional"))
    )
    (net (code "71") (name "unconnected-(U$1-PIO2_7-Pad11)") (class "Default")
      (node (ref "U$1") (pin "11") (pinfunction "PIO2_7_11") (pintype "bidirectional"))
    )
    (net (code "72") (name "unconnected-(U$1-PIO2_8-Pad12)") (class "Default")
      (node (ref "U$1") (pin "12") (pinfunction "PIO2_8_12") (pintype "bidirectional"))
    )
    (net (code "73") (name "unconnected-(U$1-PIO2_10-Pad25)") (class "Default")
      (node (ref "U$1") (pin "25") (pinfunction "PIO2_10_25") (pintype "bidirectional"))
    )
    (net (code "74") (name "unconnected-(U$1-PIO3_1{slash}~{DSR}-Pad37)") (class "Default")
      (node (ref "U$1") (pin "37") (pinfunction "PIO3_1/~{DSR}_37") (pintype "bidirectional"))
    )
    (net (code "75") (name "unconnected-(U$1-PIO3_2{slash}~{DCD}-Pad43)") (class "Default")
      (node (ref "U$1") (pin "43") (pinfunction "PIO3_2/~{DCD}_43") (pintype "bidirectional"))
    )
    (net (code "76") (name "unconnected-(U$1-PIO3_3{slash}~{RI}-Pad48)") (class "Default")
      (node (ref "U$1") (pin "48") (pinfunction "PIO3_3/~{RI}_48") (pintype "bidirectional"))
    )
    (net (code "77") (name "unconnected-(U$1-PIO3_4-Pad18)") (class "Default")
      (node (ref "U$1") (pin "18") (pinfunction "PIO3_4_18") (pintype "bidirectional"))
    )
    (net (code "78") (name "unconnected-(U$1-PIO3_5-Pad21)") (class "Default")
      (node (ref "U$1") (pin "21") (pinfunction "PIO3_5_21") (pintype "bidirectional"))
    )
    (net (code "79") (name "unconnected-(U$2-AIO1-Pad35)") (class "Default")
      (node (ref "U$2") (pin "35") (pinfunction "AIO1_35") (pintype "bidirectional"))
    )
    (net (code "80") (name "unconnected-(U$2-AIO2-Pad30)") (class "Default")
      (node (ref "U$2") (pin "30") (pinfunction "AIO2_30") (pintype "bidirectional"))
    )
    (net (code "81") (name "unconnected-(U$2-NC-Pad26)") (class "Default")
      (node (ref "U$2") (pin "26") (pinfunction "NC_26") (pintype "bidirectional"))
    )
    (net (code "82") (name "unconnected-(U$2-PCMCLK-Pad7)") (class "Default")
      (node (ref "U$2") (pin "7") (pinfunction "PCMCLK_7") (pintype "bidirectional"))
    )
    (net (code "83") (name "unconnected-(U$2-PCMIN-Pad9)") (class "Default")
      (node (ref "U$2") (pin "9") (pinfunction "PCMIN_9") (pintype "bidirectional"))
    )
    (net (code "84") (name "unconnected-(U$2-PCMOUT-Pad10)") (class "Default")
      (node (ref "U$2") (pin "10") (pinfunction "PCMOUT_10") (pintype "bidirectional"))
    )
    (net (code "85") (name "unconnected-(U$2-PCMSYNC-Pad8)") (class "Default")
      (node (ref "U$2") (pin "8") (pinfunction "PCMSYNC_8") (pintype "bidirectional"))
    )
    (net (code "86") (name "unconnected-(U$2-PIO3-Pad20)") (class "Default")
      (node (ref "U$2") (pin "20") (pinfunction "PIO3_20") (pintype "bidirectional"))
    )
    (net (code "87") (name "unconnected-(U$2-PIO6-Pad3)") (class "Default")
      (node (ref "U$2") (pin "3") (pinfunction "PIO6_3") (pintype "bidirectional"))
    )
    (net (code "88") (name "unconnected-(U$2-PIO7-Pad4)") (class "Default")
      (node (ref "U$2") (pin "4") (pinfunction "PIO7_4") (pintype "bidirectional"))
    )
    (net (code "89") (name "unconnected-(U$2-PIO8-Pad31)") (class "Default")
      (node (ref "U$2") (pin "31") (pinfunction "PIO8_31") (pintype "bidirectional"))
    )
    (net (code "90") (name "unconnected-(U$2-PIO9-Pad32)") (class "Default")
      (node (ref "U$2") (pin "32") (pinfunction "PIO9_32") (pintype "bidirectional"))
    )
    (net (code "91") (name "unconnected-(U$2-PIO10-Pad33)") (class "Default")
      (node (ref "U$2") (pin "33") (pinfunction "PIO10_33") (pintype "bidirectional"))
    )
    (net (code "92") (name "unconnected-(U$2-PIO11-Pad34)") (class "Default")
      (node (ref "U$2") (pin "34") (pinfunction "PIO11_34") (pintype "bidirectional"))
    )
    (net (code "93") (name "unconnected-(U$2-RESET-Pad5)") (class "Default")
      (node (ref "U$2") (pin "5") (pinfunction "RESET_5") (pintype "bidirectional"))
    )
    (net (code "94") (name "unconnected-(U$2-UARTCTS-Pad16)") (class "Default")
      (node (ref "U$2") (pin "16") (pinfunction "UARTCTS_16") (pintype "bidirectional"))
    )
    (net (code "95") (name "unconnected-(U$2-UARTRTS-Pad15)") (class "Default")
      (node (ref "U$2") (pin "15") (pinfunction "UARTRTS_15") (pintype "bidirectional"))
    )
    (net (code "96") (name "unconnected-(U$2-UARTRX-Pad13)") (class "Default")
      (node (ref "U$2") (pin "13") (pinfunction "UARTRX_13") (pintype "bidirectional"))
    )
    (net (code "97") (name "unconnected-(U$2-UARTTX-Pad14)") (class "Default")
      (node (ref "U$2") (pin "14") (pinfunction "UARTTX_14") (pintype "bidirectional"))
    )
    (net (code "98") (name "unconnected-(U$2-USBD+-Pad17)") (class "Default")
      (node (ref "U$2") (pin "17") (pinfunction "USBD+_17") (pintype "bidirectional"))
    )
    (net (code "99") (name "unconnected-(U$2-USBD--Pad18)") (class "Default")
      (node (ref "U$2") (pin "18") (pinfunction "USBD-_18") (pintype "bidirectional"))
    )
    (net (code "100") (name "unconnected-(U1-STAT-Pad1)") (class "Default")
      (node (ref "U1") (pin "1") (pinfunction "STAT_1") (pintype "output"))
    )
    (net (code "101") (name "unconnected-(U3-ALT-Pad5)") (class "Default")
      (node (ref "U3") (pin "5") (pinfunction "ALT_5") (pintype "bidirectional"))
    )
    (net (code "102") (name "unconnected-(U4-BP-Pad4)") (class "Default")
      (node (ref "U4") (pin "4") (pinfunction "BP_4") (pintype "input"))
    )
  )
)
